# DomoDinV1_0.net
KiCad netlist of a schematic drawn in EAGLE
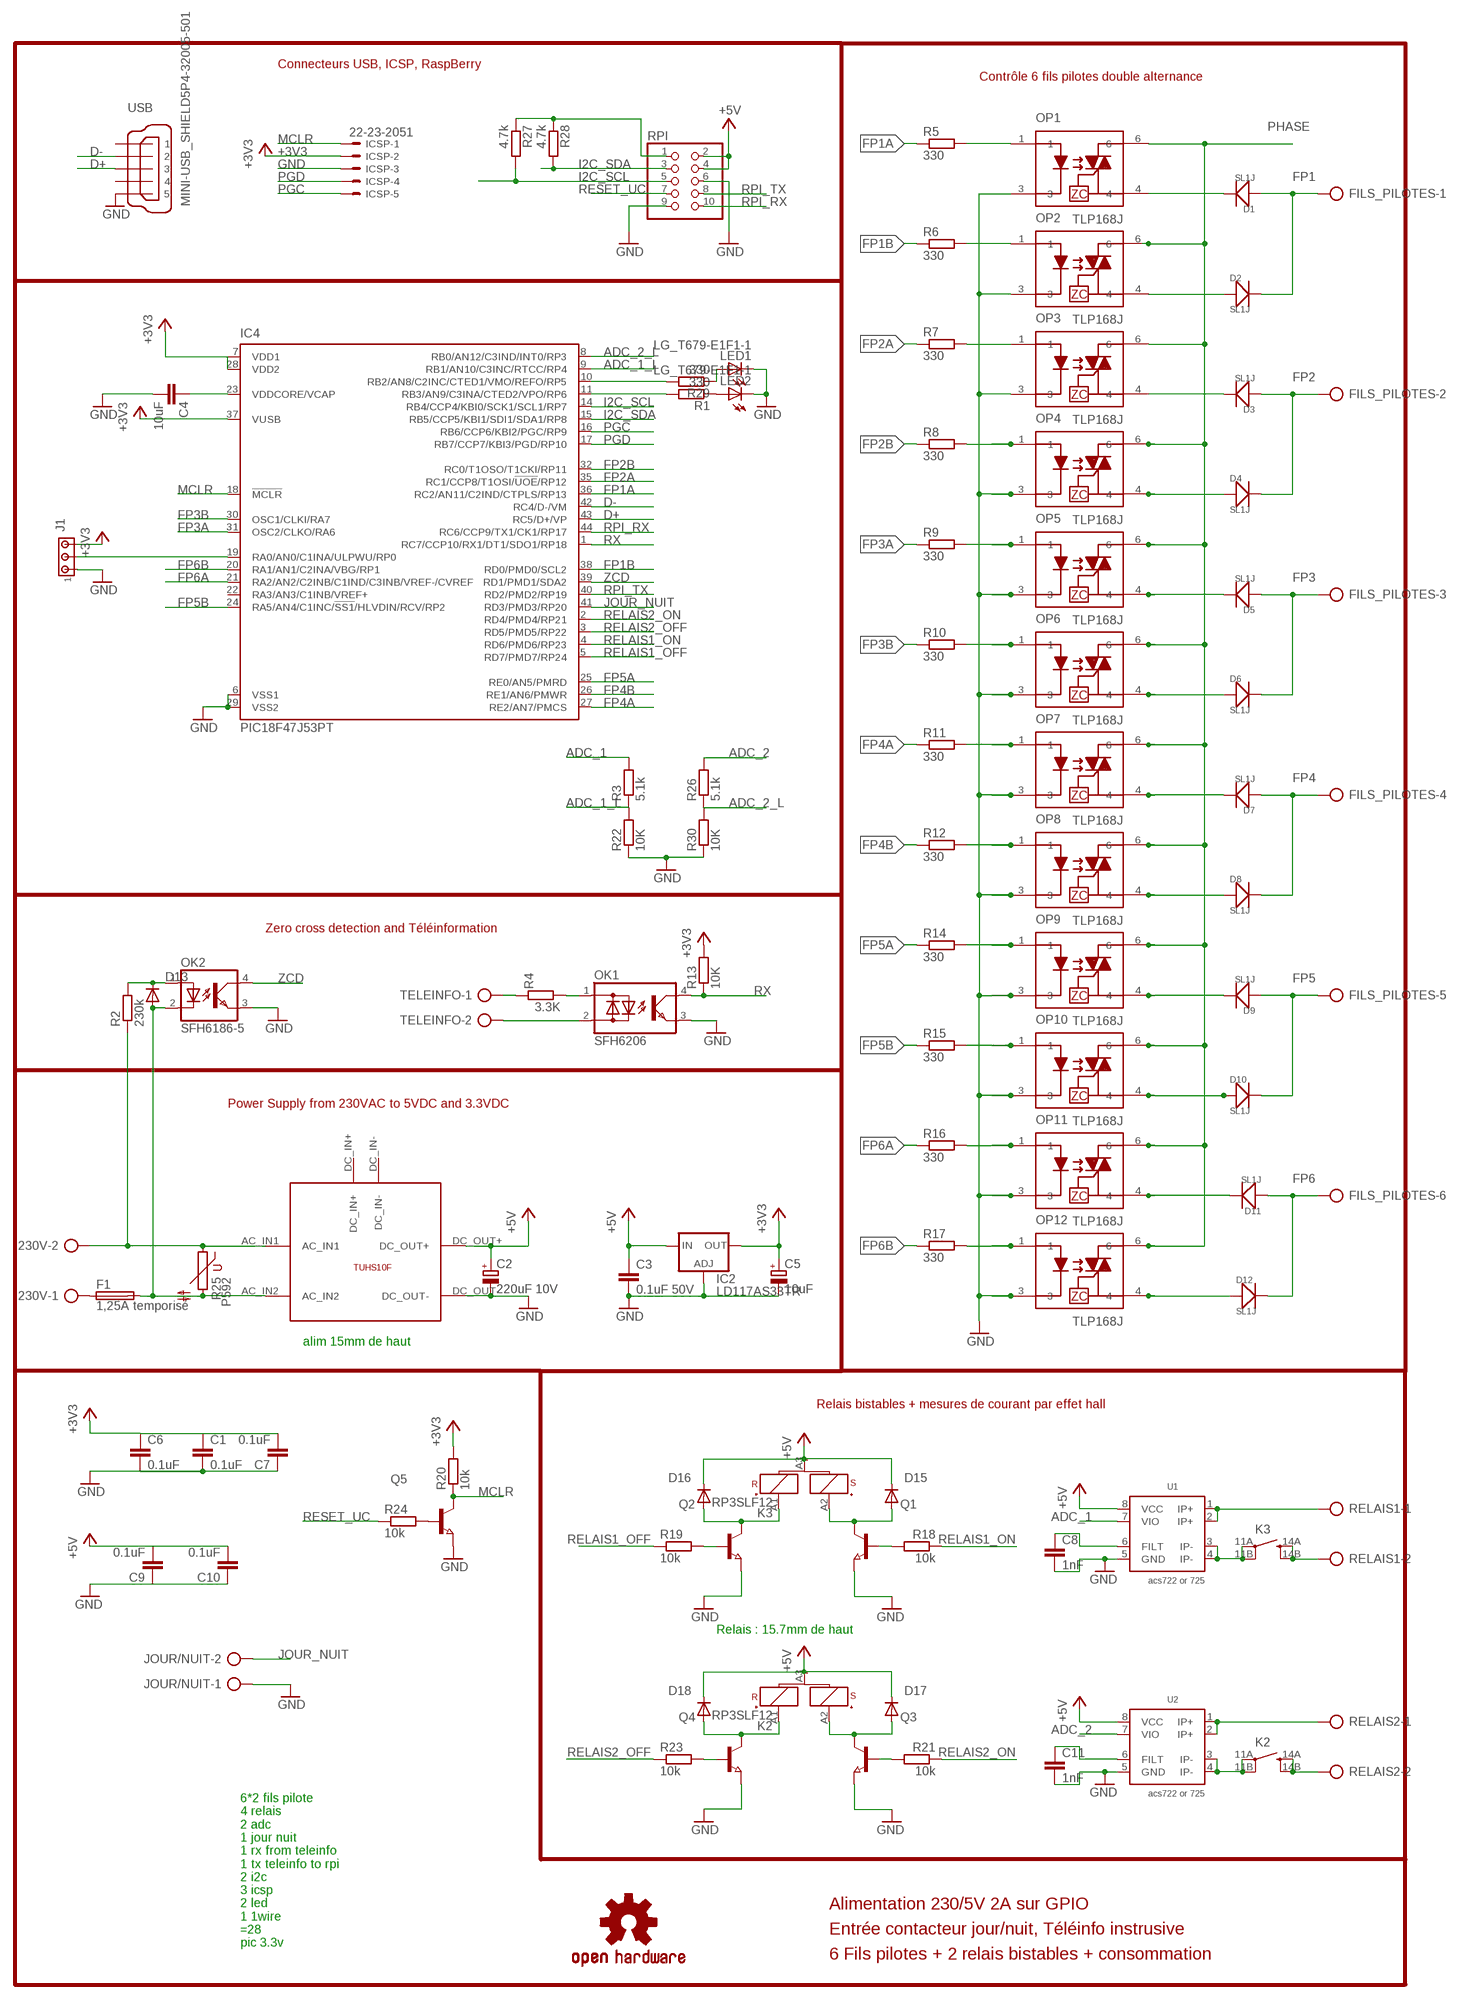
[diagram p0: schematic, sheet 1]

(export (version "E")
  (design (tool "Eeschema 10.0.6"))
  (components
    (comp (ref "230V")
      (value "AK500/2")
      (footprint "eagle-import:AK500_2")
      (libsource (lib "eagle-import") (part "AK500/2"))
    )
    (comp (ref "C1")
      (value "0.1uF")
      (footprint "eagle-import:C0603")
      (libsource (lib "eagle-import") (part "C-EUC0603"))
    )
    (comp (ref "C2")
      (value "220uF 10V")
      (footprint "eagle-import:E5-8,5")
      (libsource (lib "eagle-import") (part "CPOL-EUE5-8.5"))
    )
    (comp (ref "C3")
      (value "0.1uF 50V")
      (footprint "eagle-import:C1206")
      (libsource (lib "eagle-import") (part "C-EUC1206"))
    )
    (comp (ref "C4")
      (value "10uF")
      (footprint "eagle-import:C1210K")
      (libsource (lib "eagle-import") (part "C-EUC1210K"))
    )
    (comp (ref "C5")
      (value "10uF")
      (footprint "eagle-import:C_6032-28R")
      (libsource (lib "eagle-import") (part "CPOL-EUC/6032-28R"))
    )
    (comp (ref "C6")
      (value "0.1uF")
      (footprint "eagle-import:C0603")
      (libsource (lib "eagle-import") (part "C-EUC0603"))
    )
    (comp (ref "C7")
      (value "0.1uF")
      (footprint "eagle-import:C0603")
      (libsource (lib "eagle-import") (part "C-EUC0603"))
    )
    (comp (ref "C8")
      (value "1nF")
      (footprint "eagle-import:C0402")
      (libsource (lib "eagle-import") (part "C-EUC0402"))
    )
    (comp (ref "C9")
      (value "0.1uF")
      (footprint "eagle-import:C0603")
      (libsource (lib "eagle-import") (part "C-EUC0603"))
    )
    (comp (ref "C10")
      (value "0.1uF")
      (footprint "eagle-import:C0603")
      (libsource (lib "eagle-import") (part "C-EUC0603"))
    )
    (comp (ref "C11")
      (value "1nF")
      (footprint "eagle-import:C0402")
      (libsource (lib "eagle-import") (part "C-EUC0402"))
    )
    (comp (ref "D1")
      (value "SL1J")
      (footprint "eagle-import:DO-214AC")
      (libsource (lib "eagle-import") (part "DIODE-SMA"))
    )
    (comp (ref "D2")
      (value "SL1J")
      (footprint "eagle-import:DO-214AC")
      (libsource (lib "eagle-import") (part "DIODE-SMA"))
    )
    (comp (ref "D3")
      (value "SL1J")
      (footprint "eagle-import:DO-214AC")
      (libsource (lib "eagle-import") (part "DIODE-SMA"))
    )
    (comp (ref "D4")
      (value "SL1J")
      (footprint "eagle-import:DO-214AC")
      (libsource (lib "eagle-import") (part "DIODE-SMA"))
    )
    (comp (ref "D5")
      (value "SL1J")
      (footprint "eagle-import:DO-214AC")
      (libsource (lib "eagle-import") (part "DIODE-SMA"))
    )
    (comp (ref "D6")
      (value "SL1J")
      (footprint "eagle-import:DO-214AC")
      (libsource (lib "eagle-import") (part "DIODE-SMA"))
    )
    (comp (ref "D7")
      (value "SL1J")
      (footprint "eagle-import:DO-214AC")
      (libsource (lib "eagle-import") (part "DIODE-SMA"))
    )
    (comp (ref "D8")
      (value "SL1J")
      (footprint "eagle-import:DO-214AC")
      (libsource (lib "eagle-import") (part "DIODE-SMA"))
    )
    (comp (ref "D9")
      (value "SL1J")
      (footprint "eagle-import:DO-214AC")
      (libsource (lib "eagle-import") (part "DIODE-SMA"))
    )
    (comp (ref "D10")
      (value "SL1J")
      (footprint "eagle-import:DO-214AC")
      (libsource (lib "eagle-import") (part "DIODE-SMA"))
    )
    (comp (ref "D11")
      (value "SL1J")
      (footprint "eagle-import:DO-214AC")
      (libsource (lib "eagle-import") (part "DIODE-SMA"))
    )
    (comp (ref "D12")
      (value "SL1J")
      (footprint "eagle-import:DO-214AC")
      (libsource (lib "eagle-import") (part "DIODE-SMA"))
    )
    (comp (ref "D13")
      (value "CGRM4001-G")
      (footprint "eagle-import:SOD-123_MINI-SMA")
      (libsource (lib "eagle-import") (part "CGRM400-G1"))
    )
    (comp (ref "D15")
      (value "CGRM4001-G")
      (footprint "eagle-import:SOD-123_MINI-SMA")
      (libsource (lib "eagle-import") (part "CGRM400-G1"))
    )
    (comp (ref "D16")
      (value "CGRM4001-G")
      (footprint "eagle-import:SOD-123_MINI-SMA")
      (libsource (lib "eagle-import") (part "CGRM400-G1"))
    )
    (comp (ref "D17")
      (value "CGRM4001-G")
      (footprint "eagle-import:SOD-123_MINI-SMA")
      (libsource (lib "eagle-import") (part "CGRM400-G1"))
    )
    (comp (ref "D18")
      (value "CGRM4001-G")
      (footprint "eagle-import:SOD-123_MINI-SMA")
      (libsource (lib "eagle-import") (part "CGRM400-G1"))
    )
    (comp (ref "F1")
      (value "1,25A temporisé")
      (footprint "eagle-import:TE5")
      (libsource (lib "eagle-import") (part "TE5"))
    )
    (comp (ref "FILS_PILOTES")
      (value "AK500/6")
      (footprint "eagle-import:AK500_6")
      (libsource (lib "eagle-import") (part "AK500/6"))
    )
    (comp (ref "IC2")
      (value "LD117AS33TR")
      (footprint "eagle-import:SOT223")
      (libsource (lib "eagle-import") (part "LD117A?S33TR"))
    )
    (comp (ref "IC4")
      (value "PIC18F47J53PT")
      (footprint "eagle-import:TQFP44")
      (fields (field (name "MPN") "PIC18F47J53-I/PT"))
      (libsource (lib "eagle-import") (part "PIC18F47J53PT"))
    )
    (comp (ref "ICSP")
      (value "22-23-2051")
      (footprint "eagle-import:22-23-2051")
      (fields (field (name "MF") "MOLEX"))
      (libsource (lib "eagle-import") (part "22-23-2051"))
    )
    (comp (ref "J1")
      (value "MTA03-100")
      (footprint "eagle-import:10X03MTA")
      (libsource (lib "eagle-import") (part "MTA03-100"))
    )
    (comp (ref "JOUR/NUIT")
      (value "AK500/2")
      (footprint "eagle-import:AK500_2")
      (libsource (lib "eagle-import") (part "AK500/2"))
    )
    (comp (ref "K2")
      (value "RP3SLF12")
      (footprint "eagle-import:RP-SLF")
      (libsource (lib "eagle-import") (part "RP?SLF312"))
    )
    (comp (ref "K3")
      (value "RP3SLF12")
      (footprint "eagle-import:RP-SLF")
      (libsource (lib "eagle-import") (part "RP?SLF312"))
    )
    (comp (ref "LED1")
      (value "LG_T679-E1F1-1")
      (footprint "eagle-import:PLCC2")
      (libsource (lib "eagle-import") (part "_T679-?-1E1F1LG"))
    )
    (comp (ref "LED2")
      (value "LG_T679-E1F1-1")
      (footprint "eagle-import:PLCC2")
      (libsource (lib "eagle-import") (part "_T679-?-1E1F1LG"))
    )
    (comp (ref "LOGO1")
      (value "OSHW-LOGOL")
      (footprint "eagle-import:OSHW-LOGO-L")
      (libsource (lib "eagle-import") (part "OSHW-LOGOL"))
    )
    (comp (ref "OK1")
      (value "SFH6206")
      (footprint "eagle-import:DIL4-SMD")
      (fields (field (name "MF") "VISHAY/TELEFUNKEN") (field (name "MPN") "SFH6206-3"))
      (libsource (lib "eagle-import") (part "SFH6206"))
    )
    (comp (ref "OK2")
      (value "SFH6186-5")
      (footprint "eagle-import:SMD4-7")
      (fields (field (name "MF") "VISHAY/TELEFUNKEN"))
      (libsource (lib "eagle-import") (part "SFH618?6-5"))
    )
    (comp (ref "OP1")
      (value "TLP168J")
      (footprint "eagle-import:MFSOP-4-HANDSOLDER")
      (libsource (lib "eagle-import") (part "TLP168JBIGPAD"))
    )
    (comp (ref "OP2")
      (value "TLP168J")
      (footprint "eagle-import:MFSOP-4-HANDSOLDER")
      (libsource (lib "eagle-import") (part "TLP168JBIGPAD"))
    )
    (comp (ref "OP3")
      (value "TLP168J")
      (footprint "eagle-import:MFSOP-4-HANDSOLDER")
      (libsource (lib "eagle-import") (part "TLP168JBIGPAD"))
    )
    (comp (ref "OP4")
      (value "TLP168J")
      (footprint "eagle-import:MFSOP-4-HANDSOLDER")
      (libsource (lib "eagle-import") (part "TLP168JBIGPAD"))
    )
    (comp (ref "OP5")
      (value "TLP168J")
      (footprint "eagle-import:MFSOP-4-HANDSOLDER")
      (libsource (lib "eagle-import") (part "TLP168JBIGPAD"))
    )
    (comp (ref "OP6")
      (value "TLP168J")
      (footprint "eagle-import:MFSOP-4-HANDSOLDER")
      (libsource (lib "eagle-import") (part "TLP168JBIGPAD"))
    )
    (comp (ref "OP7")
      (value "TLP168J")
      (footprint "eagle-import:MFSOP-4-HANDSOLDER")
      (libsource (lib "eagle-import") (part "TLP168JBIGPAD"))
    )
    (comp (ref "OP8")
      (value "TLP168J")
      (footprint "eagle-import:MFSOP-4-HANDSOLDER")
      (libsource (lib "eagle-import") (part "TLP168JBIGPAD"))
    )
    (comp (ref "OP9")
      (value "TLP168J")
      (footprint "eagle-import:MFSOP-4-HANDSOLDER")
      (libsource (lib "eagle-import") (part "TLP168JBIGPAD"))
    )
    (comp (ref "OP10")
      (value "TLP168J")
      (footprint "eagle-import:MFSOP-4-HANDSOLDER")
      (libsource (lib "eagle-import") (part "TLP168JBIGPAD"))
    )
    (comp (ref "OP11")
      (value "TLP168J")
      (footprint "eagle-import:MFSOP-4-HANDSOLDER")
      (libsource (lib "eagle-import") (part "TLP168JBIGPAD"))
    )
    (comp (ref "OP12")
      (value "TLP168J")
      (footprint "eagle-import:MFSOP-4-HANDSOLDER")
      (libsource (lib "eagle-import") (part "TLP168JBIGPAD"))
    )
    (comp (ref "Q1")
      (value "NPN-TRANSISTOR_SOT23")
      (footprint "eagle-import:SOT23")
      (libsource (lib "eagle-import") (part "NPN-TRANSISTOR_SOT23"))
    )
    (comp (ref "Q2")
      (value "NPN-TRANSISTOR_SOT23")
      (footprint "eagle-import:SOT23")
      (libsource (lib "eagle-import") (part "NPN-TRANSISTOR_SOT23"))
    )
    (comp (ref "Q3")
      (value "NPN-TRANSISTOR_SOT23")
      (footprint "eagle-import:SOT23")
      (libsource (lib "eagle-import") (part "NPN-TRANSISTOR_SOT23"))
    )
    (comp (ref "Q4")
      (value "NPN-TRANSISTOR_SOT23")
      (footprint "eagle-import:SOT23")
      (libsource (lib "eagle-import") (part "NPN-TRANSISTOR_SOT23"))
    )
    (comp (ref "Q5")
      (value "NPN-TRANSISTOR_SOT23")
      (footprint "eagle-import:SOT23")
      (libsource (lib "eagle-import") (part "NPN-TRANSISTOR_SOT23"))
    )
    (comp (ref "R1")
      (value "330")
      (footprint "eagle-import:R0805")
      (libsource (lib "eagle-import") (part "R-EU_R0805"))
    )
    (comp (ref "R2")
      (value "230k")
      (footprint "eagle-import:0204_7")
      (libsource (lib "eagle-import") (part "R-EU_0204/7"))
    )
    (comp (ref "R3")
      (value "5.1k")
      (footprint "eagle-import:R0402")
      (libsource (lib "eagle-import") (part "R-EU_R0402"))
    )
    (comp (ref "R4")
      (value "3.3K")
      (footprint "eagle-import:R0805")
      (libsource (lib "eagle-import") (part "R-EU_R0805"))
    )
    (comp (ref "R5")
      (value "330")
      (footprint "eagle-import:R0805")
      (libsource (lib "eagle-import") (part "R-EU_R0805"))
    )
    (comp (ref "R6")
      (value "330")
      (footprint "eagle-import:R0805")
      (libsource (lib "eagle-import") (part "R-EU_R0805"))
    )
    (comp (ref "R7")
      (value "330")
      (footprint "eagle-import:R0805")
      (libsource (lib "eagle-import") (part "R-EU_R0805"))
    )
    (comp (ref "R8")
      (value "330")
      (footprint "eagle-import:R0805")
      (libsource (lib "eagle-import") (part "R-EU_R0805"))
    )
    (comp (ref "R9")
      (value "330")
      (footprint "eagle-import:R0805")
      (libsource (lib "eagle-import") (part "R-EU_R0805"))
    )
    (comp (ref "R10")
      (value "330")
      (footprint "eagle-import:R0805")
      (libsource (lib "eagle-import") (part "R-EU_R0805"))
    )
    (comp (ref "R11")
      (value "330")
      (footprint "eagle-import:R0805")
      (libsource (lib "eagle-import") (part "R-EU_R0805"))
    )
    (comp (ref "R12")
      (value "330")
      (footprint "eagle-import:R0805")
      (libsource (lib "eagle-import") (part "R-EU_R0805"))
    )
    (comp (ref "R13")
      (value "10K")
      (footprint "eagle-import:R0805")
      (libsource (lib "eagle-import") (part "R-EU_R0805"))
    )
    (comp (ref "R14")
      (value "330")
      (footprint "eagle-import:R0805")
      (libsource (lib "eagle-import") (part "R-EU_R0805"))
    )
    (comp (ref "R15")
      (value "330")
      (footprint "eagle-import:R0805")
      (libsource (lib "eagle-import") (part "R-EU_R0805"))
    )
    (comp (ref "R16")
      (value "330")
      (footprint "eagle-import:R0805")
      (libsource (lib "eagle-import") (part "R-EU_R0805"))
    )
    (comp (ref "R17")
      (value "330")
      (footprint "eagle-import:R0805")
      (libsource (lib "eagle-import") (part "R-EU_R0805"))
    )
    (comp (ref "R18")
      (value "10k")
      (footprint "eagle-import:R0805")
      (libsource (lib "eagle-import") (part "R-EU_R0805"))
    )
    (comp (ref "R19")
      (value "10k")
      (footprint "eagle-import:R0805")
      (libsource (lib "eagle-import") (part "R-EU_R0805"))
    )
    (comp (ref "R20")
      (value "10k")
      (footprint "eagle-import:R0805")
      (libsource (lib "eagle-import") (part "R-EU_R0805"))
    )
    (comp (ref "R21")
      (value "10k")
      (footprint "eagle-import:R0805")
      (libsource (lib "eagle-import") (part "R-EU_R0805"))
    )
    (comp (ref "R22")
      (value "10K")
      (footprint "eagle-import:R0402")
      (libsource (lib "eagle-import") (part "R-EU_R0402"))
    )
    (comp (ref "R23")
      (value "10k")
      (footprint "eagle-import:R0805")
      (libsource (lib "eagle-import") (part "R-EU_R0805"))
    )
    (comp (ref "R24")
      (value "10k")
      (footprint "eagle-import:R0805")
      (libsource (lib "eagle-import") (part "R-EU_R0805"))
    )
    (comp (ref "R25")
      (value "P592")
      (footprint "eagle-import:P592")
      (libsource (lib "eagle-import") (part "P592"))
    )
    (comp (ref "R26")
      (value "5.1k")
      (footprint "eagle-import:R0402")
      (libsource (lib "eagle-import") (part "R-EU_R0402"))
    )
    (comp (ref "R27")
      (value "4.7k")
      (footprint "eagle-import:R0805")
      (libsource (lib "eagle-import") (part "R-EU_R0805"))
    )
    (comp (ref "R28")
      (value "4.7k")
      (footprint "eagle-import:R0805")
      (libsource (lib "eagle-import") (part "R-EU_R0805"))
    )
    (comp (ref "R29")
      (value "330")
      (footprint "eagle-import:R0805")
      (libsource (lib "eagle-import") (part "R-EU_R0805"))
    )
    (comp (ref "R30")
      (value "10K")
      (footprint "eagle-import:R0402")
      (libsource (lib "eagle-import") (part "R-EU_R0402"))
    )
    (comp (ref "RELAIS1")
      (value "AK500/2")
      (footprint "eagle-import:AK500_2")
      (libsource (lib "eagle-import") (part "AK500/2"))
    )
    (comp (ref "RELAIS2")
      (value "AK500/2")
      (footprint "eagle-import:AK500_2")
      (libsource (lib "eagle-import") (part "AK500/2"))
    )
    (comp (ref "RPI")
      (value "PINHD-2X5")
      (footprint "eagle-import:2X05")
      (libsource (lib "eagle-import") (part "PINHD-2X5"))
    )
    (comp (ref "TELEINFO")
      (value "AK500/2")
      (footprint "eagle-import:AK500_2")
      (libsource (lib "eagle-import") (part "AK500/2"))
    )
    (comp (ref "U$1")
      (value "TUHS10F")
      (footprint "eagle-import:TUHS10F05")
      (libsource (lib "eagle-import") (part "TUHS10F"))
    )
    (comp (ref "U1")
      (value "acs722 or 725")
      (footprint "eagle-import:SO08")
      (libsource (lib "eagle-import") (part "ACS712"))
    )
    (comp (ref "U2")
      (value "acs722 or 725")
      (footprint "eagle-import:SO08")
      (libsource (lib "eagle-import") (part "ACS712"))
    )
    (comp (ref "USB")
      (value "MINI-USB_SHIELD5P4-32005-501")
      (footprint "eagle-import:32005-501")
      (libsource (lib "eagle-import") (part "MINI-USB_SHIELD5P4-32005-501"))
    )
  )
  (nets
    (net (code "1") (name "+3V3") (class "Default")
      (node (ref "C1") (pin "1") (pinfunction "1_1") (pintype "passive"))
      (node (ref "C5") (pin "+") (pinfunction "+_+") (pintype "passive"))
      (node (ref "C6") (pin "1") (pinfunction "1_1") (pintype "passive"))
      (node (ref "C7") (pin "2") (pinfunction "2_2") (pintype "passive"))
      (node (ref "IC2") (pin "4") (pinfunction "OUT_4") (pintype "passive"))
      (node (ref "IC4") (pin "28") (pinfunction "VDD2_28") (pintype "input"))
      (node (ref "IC4") (pin "37") (pinfunction "VUSB_37") (pintype "input"))
      (node (ref "IC4") (pin "7") (pinfunction "VDD1_7") (pintype "input"))
      (node (ref "ICSP") (pin "2") (pinfunction "S_2") (pintype "passive"))
      (node (ref "J1") (pin "3") (pinfunction "3_3") (pintype "passive"))
      (node (ref "R13") (pin "2") (pinfunction "2_2") (pintype "passive"))
      (node (ref "R20") (pin "2") (pinfunction "2_2") (pintype "passive"))
    )
    (net (code "2") (name "+5V") (class "Default")
      (node (ref "C10") (pin "2") (pinfunction "2_2") (pintype "passive"))
      (node (ref "C2") (pin "+") (pinfunction "+_+") (pintype "passive"))
      (node (ref "C3") (pin "1") (pinfunction "1_1") (pintype "passive"))
      (node (ref "C9") (pin "2") (pinfunction "2_2") (pintype "passive"))
      (node (ref "D15") (pin "C") (pinfunction "C_C") (pintype "passive"))
      (node (ref "D16") (pin "C") (pinfunction "C_C") (pintype "passive"))
      (node (ref "D17") (pin "C") (pinfunction "C_C") (pintype "passive"))
      (node (ref "D18") (pin "C") (pinfunction "C_C") (pintype "passive"))
      (node (ref "IC2") (pin "3") (pinfunction "IN_3") (pintype "input"))
      (node (ref "K2") (pin "A3") (pinfunction "-_A3") (pintype "passive"))
      (node (ref "K3") (pin "A3") (pinfunction "-_A3") (pintype "passive"))
      (node (ref "RPI") (pin "2") (pinfunction "2_2") (pintype "passive"))
      (node (ref "RPI") (pin "4") (pinfunction "4_4") (pintype "passive"))
      (node (ref "U$1") (pin "DC_OUT+") (pinfunction "DC_OUT+_DC_OUT+") (pintype "bidirectional"))
      (node (ref "U1") (pin "8") (pinfunction "VCC_8") (pintype "bidirectional"))
      (node (ref "U2") (pin "8") (pinfunction "VCC_8") (pintype "bidirectional"))
    )
    (net (code "3") (name "/ADC_1") (class "Default")
      (node (ref "R3") (pin "2") (pinfunction "2_2") (pintype "passive"))
      (node (ref "U1") (pin "7") (pinfunction "VIO_7") (pintype "bidirectional"))
    )
    (net (code "4") (name "/ADC_1_L") (class "Default")
      (node (ref "IC4") (pin "9") (pinfunction "RB1/AN10/C3INC/RTCC/RP4_9") (pintype "bidirectional"))
      (node (ref "R22") (pin "2") (pinfunction "2_2") (pintype "passive"))
      (node (ref "R3") (pin "1") (pinfunction "1_1") (pintype "passive"))
    )
    (net (code "5") (name "/ADC_2") (class "Default")
      (node (ref "R26") (pin "2") (pinfunction "2_2") (pintype "passive"))
      (node (ref "U2") (pin "7") (pinfunction "VIO_7") (pintype "bidirectional"))
    )
    (net (code "6") (name "/ADC_2_L") (class "Default")
      (node (ref "IC4") (pin "8") (pinfunction "RB0/AN12/C3IND/INT0/RP3_8") (pintype "bidirectional"))
      (node (ref "R26") (pin "1") (pinfunction "1_1") (pintype "passive"))
      (node (ref "R30") (pin "2") (pinfunction "2_2") (pintype "passive"))
    )
    (net (code "7") (name "/D+") (class "Default")
      (node (ref "IC4") (pin "43") (pinfunction "RC5/D+/VP_43") (pintype "bidirectional"))
      (node (ref "USB") (pin "3") (pinfunction "3_3") (pintype "passive"))
    )
    (net (code "8") (name "/D-") (class "Default")
      (node (ref "IC4") (pin "42") (pinfunction "RC4/D-/VM_42") (pintype "bidirectional"))
      (node (ref "USB") (pin "2") (pinfunction "2_2") (pintype "passive"))
    )
    (net (code "9") (name "/FP1") (class "Default")
      (node (ref "D1") (pin "1") (pinfunction "+_1") (pintype "passive"))
      (node (ref "D2") (pin "2") (pinfunction "-_2") (pintype "passive"))
      (node (ref "FILS_PILOTES") (pin "1") (pinfunction "KL_1") (pintype "passive"))
    )
    (net (code "10") (name "/FP2") (class "Default")
      (node (ref "D3") (pin "1") (pinfunction "+_1") (pintype "passive"))
      (node (ref "D4") (pin "2") (pinfunction "-_2") (pintype "passive"))
      (node (ref "FILS_PILOTES") (pin "2") (pinfunction "KL_2") (pintype "passive"))
    )
    (net (code "11") (name "/FP3") (class "Default")
      (node (ref "D5") (pin "1") (pinfunction "+_1") (pintype "passive"))
      (node (ref "D6") (pin "2") (pinfunction "-_2") (pintype "passive"))
      (node (ref "FILS_PILOTES") (pin "3") (pinfunction "KL_3") (pintype "passive"))
    )
    (net (code "12") (name "/FP4") (class "Default")
      (node (ref "D7") (pin "1") (pinfunction "+_1") (pintype "passive"))
      (node (ref "D8") (pin "2") (pinfunction "-_2") (pintype "passive"))
      (node (ref "FILS_PILOTES") (pin "4") (pinfunction "KL_4") (pintype "passive"))
    )
    (net (code "13") (name "/FP5") (class "Default")
      (node (ref "D10") (pin "2") (pinfunction "-_2") (pintype "passive"))
      (node (ref "D9") (pin "1") (pinfunction "+_1") (pintype "passive"))
      (node (ref "FILS_PILOTES") (pin "5") (pinfunction "KL_5") (pintype "passive"))
    )
    (net (code "14") (name "/FP6") (class "Default")
      (node (ref "D11") (pin "1") (pinfunction "+_1") (pintype "passive"))
      (node (ref "D12") (pin "2") (pinfunction "-_2") (pintype "passive"))
      (node (ref "FILS_PILOTES") (pin "6") (pinfunction "KL_6") (pintype "passive"))
    )
    (net (code "15") (name "/I2C_SCL") (class "Default")
      (node (ref "IC4") (pin "14") (pinfunction "RB4/CCP4/KBI0/SCK1/SCL1/RP7_14") (pintype "bidirectional"))
      (node (ref "R27") (pin "2") (pinfunction "2_2") (pintype "passive"))
      (node (ref "RPI") (pin "5") (pinfunction "5_5") (pintype "passive"))
    )
    (net (code "16") (name "/I2C_SDA") (class "Default")
      (node (ref "IC4") (pin "15") (pinfunction "RB5/CCP5/KBI1/SDI1/SDA1/RP8_15") (pintype "bidirectional"))
      (node (ref "R28") (pin "2") (pinfunction "2_2") (pintype "passive"))
      (node (ref "RPI") (pin "3") (pinfunction "3_3") (pintype "passive"))
    )
    (net (code "17") (name "/JOUR_NUIT") (class "Default")
      (node (ref "IC4") (pin "41") (pinfunction "RD3/PMD3/RP20_41") (pintype "bidirectional"))
      (node (ref "JOUR/NUIT") (pin "2") (pinfunction "KL_2") (pintype "passive"))
    )
    (net (code "18") (name "/MCLR") (class "Default")
      (node (ref "IC4") (pin "18") (pinfunction "~{MCLR}_18") (pintype "input"))
      (node (ref "ICSP") (pin "1") (pinfunction "S_1") (pintype "passive"))
      (node (ref "Q5") (pin "3") (pinfunction "C_3") (pintype "passive"))
      (node (ref "R20") (pin "1") (pinfunction "1_1") (pintype "passive"))
    )
    (net (code "19") (name "/PGC") (class "Default")
      (node (ref "IC4") (pin "16") (pinfunction "RB6/CCP6/KBI2/PGC/RP9_16") (pintype "bidirectional"))
      (node (ref "ICSP") (pin "5") (pinfunction "S_5") (pintype "passive"))
    )
    (net (code "20") (name "/PGD") (class "Default")
      (node (ref "IC4") (pin "17") (pinfunction "RB7/CCP7/KBI3/PGD/RP10_17") (pintype "bidirectional"))
      (node (ref "ICSP") (pin "4") (pinfunction "S_4") (pintype "passive"))
    )
    (net (code "21") (name "/PHASE") (class "Default")
      (node (ref "D13") (pin "A") (pinfunction "A_A") (pintype "passive"))
      (node (ref "F1") (pin "2") (pinfunction "2_2") (pintype "passive"))
      (node (ref "OK2") (pin "2") (pinfunction "C_2") (pintype "passive"))
      (node (ref "OP1") (pin "6") (pinfunction "6_6") (pintype "bidirectional"))
      (node (ref "OP10") (pin "6") (pinfunction "6_6") (pintype "bidirectional"))
      (node (ref "OP11") (pin "6") (pinfunction "6_6") (pintype "bidirectional"))
      (node (ref "OP12") (pin "6") (pinfunction "6_6") (pintype "bidirectional"))
      (node (ref "OP2") (pin "6") (pinfunction "6_6") (pintype "bidirectional"))
      (node (ref "OP3") (pin "6") (pinfunction "6_6") (pintype "bidirectional"))
      (node (ref "OP4") (pin "6") (pinfunction "6_6") (pintype "bidirectional"))
      (node (ref "OP5") (pin "6") (pinfunction "6_6") (pintype "bidirectional"))
      (node (ref "OP6") (pin "6") (pinfunction "6_6") (pintype "bidirectional"))
      (node (ref "OP7") (pin "6") (pinfunction "6_6") (pintype "bidirectional"))
      (node (ref "OP8") (pin "6") (pinfunction "6_6") (pintype "bidirectional"))
      (node (ref "OP9") (pin "6") (pinfunction "6_6") (pintype "bidirectional"))
      (node (ref "R25") (pin "2") (pinfunction "2_2") (pintype "passive"))
      (node (ref "U$1") (pin "AC_IN2") (pinfunction "AC_IN2_AC_IN2") (pintype "bidirectional"))
    )
    (net (code "22") (name "/RELAIS1_OFF") (class "Default")
      (node (ref "IC4") (pin "5") (pinfunction "RD7/PMD7/RP24_5") (pintype "bidirectional"))
      (node (ref "R19") (pin "1") (pinfunction "1_1") (pintype "passive"))
    )
    (net (code "23") (name "/RELAIS1_ON") (class "Default")
      (node (ref "IC4") (pin "4") (pinfunction "RD6/PMD6/RP23_4") (pintype "bidirectional"))
      (node (ref "R18") (pin "1") (pinfunction "1_1") (pintype "passive"))
    )
    (net (code "24") (name "/RELAIS2_OFF") (class "Default")
      (node (ref "IC4") (pin "3") (pinfunction "RD5/PMD5/RP22_3") (pintype "bidirectional"))
      (node (ref "R23") (pin "1") (pinfunction "1_1") (pintype "passive"))
    )
    (net (code "25") (name "/RELAIS2_ON") (class "Default")
      (node (ref "IC4") (pin "2") (pinfunction "RD4/PMD4/RP21_2") (pintype "bidirectional"))
      (node (ref "R21") (pin "1") (pinfunction "1_1") (pintype "passive"))
    )
    (net (code "26") (name "/RESET_UC") (class "Default")
      (node (ref "R24") (pin "1") (pinfunction "1_1") (pintype "passive"))
      (node (ref "RPI") (pin "7") (pinfunction "7_7") (pintype "passive"))
    )
    (net (code "27") (name "/RPI_RX") (class "Default")
      (node (ref "IC4") (pin "44") (pinfunction "RC6/CCP9/TX1/CK1/RP17_44") (pintype "bidirectional"))
      (node (ref "RPI") (pin "10") (pinfunction "10_10") (pintype "passive"))
    )
    (net (code "28") (name "/RPI_TX") (class "Default")
      (node (ref "IC4") (pin "40") (pinfunction "RD2/PMD2/RP19_40") (pintype "bidirectional"))
      (node (ref "RPI") (pin "8") (pinfunction "8_8") (pintype "passive"))
    )
    (net (code "29") (name "/RX") (class "Default")
      (node (ref "IC4") (pin "1") (pinfunction "RC7/CCP10/RX1/DT1/SDO1/RP18_1") (pintype "bidirectional"))
      (node (ref "OK1") (pin "4") (pinfunction "C_4") (pintype "passive"))
      (node (ref "R13") (pin "1") (pinfunction "1_1") (pintype "passive"))
    )
    (net (code "30") (name "/ZCD") (class "Default")
      (node (ref "IC4") (pin "39") (pinfunction "RD1/PMD1/SDA2_39") (pintype "bidirectional"))
      (node (ref "OK2") (pin "4") (pinfunction "COL_4") (pintype "passive"))
    )
    (net (code "31") (name "FP1A") (class "Default")
      (node (ref "IC4") (pin "36") (pinfunction "RC2/AN11/C2IND/CTPLS/RP13_36") (pintype "bidirectional"))
      (node (ref "R5") (pin "1") (pinfunction "1_1") (pintype "passive"))
    )
    (net (code "32") (name "FP1B") (class "Default")
      (node (ref "IC4") (pin "38") (pinfunction "RD0/PMD0/SCL2_38") (pintype "bidirectional"))
      (node (ref "R6") (pin "1") (pinfunction "1_1") (pintype "passive"))
    )
    (net (code "33") (name "FP2A") (class "Default")
      (node (ref "IC4") (pin "35") (pinfunction "RC1/CCP8/T1OSI/~{UOE}/RP12_35") (pintype "bidirectional"))
      (node (ref "R7") (pin "1") (pinfunction "1_1") (pintype "passive"))
    )
    (net (code "34") (name "FP2B") (class "Default")
      (node (ref "IC4") (pin "32") (pinfunction "RC0/T1OSO/T1CKI/RP11_32") (pintype "bidirectional"))
      (node (ref "R8") (pin "1") (pinfunction "1_1") (pintype "passive"))
    )
    (net (code "35") (name "FP3A") (class "Default")
      (node (ref "IC4") (pin "31") (pinfunction "OSC2/CLKO/RA6_31") (pintype "bidirectional"))
      (node (ref "R9") (pin "1") (pinfunction "1_1") (pintype "passive"))
    )
    (net (code "36") (name "FP3B") (class "Default")
      (node (ref "IC4") (pin "30") (pinfunction "OSC1/CLKI/RA7_30") (pintype "bidirectional"))
      (node (ref "R10") (pin "1") (pinfunction "1_1") (pintype "passive"))
    )
    (net (code "37") (name "FP4A") (class "Default")
      (node (ref "IC4") (pin "27") (pinfunction "RE2/AN7/PMCS_27") (pintype "bidirectional"))
      (node (ref "R11") (pin "1") (pinfunction "1_1") (pintype "passive"))
    )
    (net (code "38") (name "FP4B") (class "Default")
      (node (ref "IC4") (pin "26") (pinfunction "RE1/AN6/PMWR_26") (pintype "bidirectional"))
      (node (ref "R12") (pin "1") (pinfunction "1_1") (pintype "passive"))
    )
    (net (code "39") (name "FP5A") (class "Default")
      (node (ref "IC4") (pin "25") (pinfunction "RE0/AN5/PMRD_25") (pintype "bidirectional"))
      (node (ref "R14") (pin "1") (pinfunction "1_1") (pintype "passive"))
    )
    (net (code "40") (name "FP5B") (class "Default")
      (node (ref "IC4") (pin "24") (pinfunction "RA5/AN4/C1INC/~{SS1}/HLVDIN/RCV/RP2_24") (pintype "bidirectional"))
      (node (ref "R15") (pin "1") (pinfunction "1_1") (pintype "passive"))
    )
    (net (code "41") (name "FP6A") (class "Default")
      (node (ref "IC4") (pin "21") (pinfunction "RA2/AN2/C2INB/C1IND/C3INB/VREF-/CVREF_21") (pintype "bidirectional"))
      (node (ref "R16") (pin "1") (pinfunction "1_1") (pintype "passive"))
    )
    (net (code "42") (name "FP6B") (class "Default")
      (node (ref "IC4") (pin "20") (pinfunction "RA1/AN1/C2INA/VBG/RP1_20") (pintype "bidirectional"))
      (node (ref "R17") (pin "1") (pinfunction "1_1") (pintype "passive"))
    )
    (net (code "43") (name "GND") (class "Default")
      (node (ref "C1") (pin "2") (pinfunction "2_2") (pintype "passive"))
      (node (ref "C10") (pin "1") (pinfunction "1_1") (pintype "passive"))
      (node (ref "C11") (pin "2") (pinfunction "2_2") (pintype "passive"))
      (node (ref "C2") (pin "-") (pinfunction "-_-") (pintype "passive"))
      (node (ref "C3") (pin "2") (pinfunction "2_2") (pintype "passive"))
      (node (ref "C4") (pin "2") (pinfunction "2_2") (pintype "passive"))
      (node (ref "C5") (pin "-") (pinfunction "-_-") (pintype "passive"))
      (node (ref "C6") (pin "2") (pinfunction "2_2") (pintype "passive"))
      (node (ref "C7") (pin "1") (pinfunction "1_1") (pintype "passive"))
      (node (ref "C8") (pin "2") (pinfunction "2_2") (pintype "passive"))
      (node (ref "C9") (pin "1") (pinfunction "1_1") (pintype "passive"))
      (node (ref "IC2") (pin "1") (pinfunction "ADJ_1") (pintype "input"))
      (node (ref "IC4") (pin "29") (pinfunction "VSS2_29") (pintype "input"))
      (node (ref "IC4") (pin "6") (pinfunction "VSS1_6") (pintype "input"))
      (node (ref "ICSP") (pin "3") (pinfunction "S_3") (pintype "passive"))
      (node (ref "J1") (pin "1") (pinfunction "1_1") (pintype "passive"))
      (node (ref "JOUR/NUIT") (pin "1") (pinfunction "KL_1") (pintype "passive"))
      (node (ref "LED1") (pin "C") (pinfunction "C_C") (pintype "passive"))
      (node (ref "LED2") (pin "C") (pinfunction "C_C") (pintype "passive"))
      (node (ref "OK1") (pin "3") (pinfunction "E_3") (pintype "passive"))
      (node (ref "OK2") (pin "3") (pinfunction "EMIT_3") (pintype "passive"))
      (node (ref "OP1") (pin "3") (pinfunction "3_3") (pintype "bidirectional"))
      (node (ref "OP10") (pin "3") (pinfunction "3_3") (pintype "bidirectional"))
      (node (ref "OP11") (pin "3") (pinfunction "3_3") (pintype "bidirectional"))
      (node (ref "OP12") (pin "3") (pinfunction "3_3") (pintype "bidirectional"))
      (node (ref "OP2") (pin "3") (pinfunction "3_3") (pintype "bidirectional"))
      (node (ref "OP3") (pin "3") (pinfunction "3_3") (pintype "bidirectional"))
      (node (ref "OP4") (pin "3") (pinfunction "3_3") (pintype "bidirectional"))
      (node (ref "OP5") (pin "3") (pinfunction "3_3") (pintype "bidirectional"))
      (node (ref "OP6") (pin "3") (pinfunction "3_3") (pintype "bidirectional"))
      (node (ref "OP7") (pin "3") (pinfunction "3_3") (pintype "bidirectional"))
      (node (ref "OP8") (pin "3") (pinfunction "3_3") (pintype "bidirectional"))
      (node (ref "OP9") (pin "3") (pinfunction "3_3") (pintype "bidirectional"))
      (node (ref "Q1") (pin "2") (pinfunction "E_2") (pintype "passive"))
      (node (ref "Q2") (pin "2") (pinfunction "E_2") (pintype "passive"))
      (node (ref "Q3") (pin "2") (pinfunction "E_2") (pintype "passive"))
      (node (ref "Q4") (pin "2") (pinfunction "E_2") (pintype "passive"))
      (node (ref "Q5") (pin "2") (pinfunction "E_2") (pintype "passive"))
      (node (ref "R22") (pin "1") (pinfunction "1_1") (pintype "passive"))
      (node (ref "R30") (pin "1") (pinfunction "1_1") (pintype "passive"))
      (node (ref "RPI") (pin "6") (pinfunction "6_6") (pintype "passive"))
      (node (ref "RPI") (pin "9") (pinfunction "9_9") (pintype "passive"))
      (node (ref "U$1") (pin "DC_OUT-") (pinfunction "DC_OUT-_DC_OUT-") (pintype "bidirectional"))
      (node (ref "U1") (pin "5") (pinfunction "GND_5") (pintype "bidirectional"))
      (node (ref "U2") (pin "5") (pinfunction "GND_5") (pintype "bidirectional"))
      (node (ref "USB") (pin "5") (pinfunction "5_5") (pintype "passive"))
    )
    (net (code "44") (name "Net-(230VA-KL)") (class "Default")
      (node (ref "230V") (pin "1") (pinfunction "KL_1") (pintype "passive"))
      (node (ref "F1") (pin "1") (pinfunction "1_1") (pintype "passive"))
    )
    (net (code "45") (name "Net-(230VB-KL)") (class "Default")
      (node (ref "230V") (pin "2") (pinfunction "KL_2") (pintype "passive"))
      (node (ref "R2") (pin "1") (pinfunction "1_1") (pintype "passive"))
      (node (ref "R25") (pin "1") (pinfunction "1_1") (pintype "passive"))
      (node (ref "U$1") (pin "AC_IN1") (pinfunction "AC_IN1_AC_IN1") (pintype "bidirectional"))
    )
    (net (code "46") (name "Net-(D1--)") (class "Default")
      (node (ref "D1") (pin "2") (pinfunction "-_2") (pintype "passive"))
      (node (ref "OP1") (pin "4") (pinfunction "4_4") (pintype "bidirectional"))
    )
    (net (code "47") (name "Net-(D2-+)") (class "Default")
      (node (ref "D2") (pin "1") (pinfunction "+_1") (pintype "passive"))
      (node (ref "OP2") (pin "4") (pinfunction "4_4") (pintype "bidirectional"))
    )
    (net (code "48") (name "Net-(D3--)") (class "Default")
      (node (ref "D3") (pin "2") (pinfunction "-_2") (pintype "passive"))
      (node (ref "OP3") (pin "4") (pinfunction "4_4") (pintype "bidirectional"))
    )
    (net (code "49") (name "Net-(D4-+)") (class "Default")
      (node (ref "D4") (pin "1") (pinfunction "+_1") (pintype "passive"))
      (node (ref "OP4") (pin "4") (pinfunction "4_4") (pintype "bidirectional"))
    )
    (net (code "50") (name "Net-(D5--)") (class "Default")
      (node (ref "D5") (pin "2") (pinfunction "-_2") (pintype "passive"))
      (node (ref "OP5") (pin "4") (pinfunction "4_4") (pintype "bidirectional"))
    )
    (net (code "51") (name "Net-(D6-+)") (class "Default")
      (node (ref "D6") (pin "1") (pinfunction "+_1") (pintype "passive"))
      (node (ref "OP6") (pin "4") (pinfunction "4_4") (pintype "bidirectional"))
    )
    (net (code "52") (name "Net-(D7--)") (class "Default")
      (node (ref "D7") (pin "2") (pinfunction "-_2") (pintype "passive"))
      (node (ref "OP7") (pin "4") (pinfunction "4_4") (pintype "bidirectional"))
    )
    (net (code "53") (name "Net-(D8-+)") (class "Default")
      (node (ref "D8") (pin "1") (pinfunction "+_1") (pintype "passive"))
      (node (ref "OP8") (pin "4") (pinfunction "4_4") (pintype "bidirectional"))
    )
    (net (code "54") (name "Net-(D9--)") (class "Default")
      (node (ref "D9") (pin "2") (pinfunction "-_2") (pintype "passive"))
      (node (ref "OP9") (pin "4") (pinfunction "4_4") (pintype "bidirectional"))
    )
    (net (code "55") (name "Net-(D10-+)") (class "Default")
      (node (ref "D10") (pin "1") (pinfunction "+_1") (pintype "passive"))
      (node (ref "OP10") (pin "4") (pinfunction "4_4") (pintype "bidirectional"))
    )
    (net (code "56") (name "Net-(D11--)") (class "Default")
      (node (ref "D11") (pin "2") (pinfunction "-_2") (pintype "passive"))
      (node (ref "OP11") (pin "4") (pinfunction "4_4") (pintype "bidirectional"))
    )
    (net (code "57") (name "Net-(D12-+)") (class "Default")
      (node (ref "D12") (pin "1") (pinfunction "+_1") (pintype "passive"))
      (node (ref "OP12") (pin "4") (pinfunction "4_4") (pintype "bidirectional"))
    )
    (net (code "58") (name "Net-(IC4-RA0{slash}AN0{slash}C1INA{slash}ULPWU{slash}RP0)") (class "Default")
      (node (ref "IC4") (pin "19") (pinfunction "RA0/AN0/C1INA/ULPWU/RP0_19") (pintype "bidirectional"))
      (node (ref "J1") (pin "2") (pinfunction "2_2") (pintype "passive"))
    )
    (net (code "59") (name "Net-(IC4-RB2{slash}AN8{slash}C2INC{slash}CTED1{slash}VMO{slash}REFO{slash}RP5)") (class "Default")
      (node (ref "IC4") (pin "10") (pinfunction "RB2/AN8/C2INC/CTED1/VMO/REFO/RP5_10") (pintype "bidirectional"))
      (node (ref "R29") (pin "2") (pinfunction "2_2") (pintype "passive"))
    )
    (net (code "60") (name "Net-(IC4-RB3{slash}AN9{slash}C3INA{slash}CTED2{slash}VPO{slash}RP6)") (class "Default")
      (node (ref "IC4") (pin "11") (pinfunction "RB3/AN9/C3INA/CTED2/VPO/RP6_11") (pintype "bidirectional"))
      (node (ref "R1") (pin "2") (pinfunction "2_2") (pintype "passive"))
    )
    (net (code "61") (name "Net-(IC4-VDDCORE{slash}VCAP)") (class "Default")
      (node (ref "C4") (pin "1") (pinfunction "1_1") (pintype "passive"))
      (node (ref "IC4") (pin "23") (pinfunction "VDDCORE/VCAP_23") (pintype "input"))
    )
    (net (code "62") (name "Net-(K2A-R+)") (class "Default")
      (node (ref "D18") (pin "A") (pinfunction "A_A") (pintype "passive"))
      (node (ref "K2") (pin "A1") (pinfunction "R+_A1") (pintype "passive"))
      (node (ref "Q4") (pin "3") (pinfunction "C_3") (pintype "passive"))
    )
    (net (code "63") (name "Net-(K2A-S+)") (class "Default")
      (node (ref "D17") (pin "A") (pinfunction "A_A") (pintype "passive"))
      (node (ref "K2") (pin "A2") (pinfunction "S+_A2") (pintype "passive"))
      (node (ref "Q3") (pin "3") (pinfunction "C_3") (pintype "passive"))
    )
    (net (code "64") (name "Net-(K2B-PA)") (class "Default")
      (node (ref "K2") (pin "11A") (pinfunction "PA_11A") (pintype "passive"))
      (node (ref "K2") (pin "11B") (pinfunction "PB_11B") (pintype "passive"))
      (node (ref "U2") (pin "3") (pinfunction "IP-_3") (pintype "bidirectional"))
      (node (ref "U2") (pin "4") (pinfunction "IP-_4") (pintype "bidirectional"))
    )
    (net (code "65") (name "Net-(K2B-SA)") (class "Default")
      (node (ref "K2") (pin "14A") (pinfunction "SA_14A") (pintype "passive"))
      (node (ref "K2") (pin "14B") (pinfunction "SB_14B") (pintype "passive"))
      (node (ref "RELAIS2") (pin "2") (pinfunction "KL_2") (pintype "passive"))
    )
    (net (code "66") (name "Net-(K3A-R+)") (class "Default")
      (node (ref "D16") (pin "A") (pinfunction "A_A") (pintype "passive"))
      (node (ref "K3") (pin "A1") (pinfunction "R+_A1") (pintype "passive"))
      (node (ref "Q2") (pin "3") (pinfunction "C_3") (pintype "passive"))
    )
    (net (code "67") (name "Net-(K3A-S+)") (class "Default")
      (node (ref "D15") (pin "A") (pinfunction "A_A") (pintype "passive"))
      (node (ref "K3") (pin "A2") (pinfunction "S+_A2") (pintype "passive"))
      (node (ref "Q1") (pin "3") (pinfunction "C_3") (pintype "passive"))
    )
    (net (code "68") (name "Net-(K3B-PA)") (class "Default")
      (node (ref "K3") (pin "11A") (pinfunction "PA_11A") (pintype "passive"))
      (node (ref "K3") (pin "11B") (pinfunction "PB_11B") (pintype "passive"))
      (node (ref "U1") (pin "3") (pinfunction "IP-_3") (pintype "bidirectional"))
      (node (ref "U1") (pin "4") (pinfunction "IP-_4") (pintype "bidirectional"))
    )
    (net (code "69") (name "Net-(K3B-SA)") (class "Default")
      (node (ref "K3") (pin "14A") (pinfunction "SA_14A") (pintype "passive"))
      (node (ref "K3") (pin "14B") (pinfunction "SB_14B") (pintype "passive"))
      (node (ref "RELAIS1") (pin "2") (pinfunction "KL_2") (pintype "passive"))
    )
    (net (code "70") (name "Net-(LED1-PadA)") (class "Default")
      (node (ref "LED1") (pin "A") (pinfunction "A_A") (pintype "passive"))
      (node (ref "R29") (pin "1") (pinfunction "1_1") (pintype "passive"))
    )
    (net (code "71") (name "Net-(LED2-PadA)") (class "Default")
      (node (ref "LED2") (pin "A") (pinfunction "A_A") (pintype "passive"))
      (node (ref "R1") (pin "1") (pinfunction "1_1") (pintype "passive"))
    )
    (net (code "72") (name "Net-(OK1-AC1)") (class "Default")
      (node (ref "OK1") (pin "1") (pinfunction "AC1_1") (pintype "passive"))
      (node (ref "R4") (pin "2") (pinfunction "2_2") (pintype "passive"))
    )
    (net (code "73") (name "Net-(OK1-AC2)") (class "Default")
      (node (ref "OK1") (pin "2") (pinfunction "AC2_2") (pintype "passive"))
      (node (ref "TELEINFO") (pin "2") (pinfunction "KL_2") (pintype "passive"))
    )
    (net (code "74") (name "Net-(OK2-A)") (class "Default")
      (node (ref "D13") (pin "C") (pinfunction "C_C") (pintype "passive"))
      (node (ref "OK2") (pin "1") (pinfunction "A_1") (pintype "passive"))
      (node (ref "R2") (pin "2") (pinfunction "2_2") (pintype "passive"))
    )
    (net (code "75") (name "Net-(OP1-Pad1)") (class "Default")
      (node (ref "OP1") (pin "1") (pinfunction "1_1") (pintype "bidirectional"))
      (node (ref "R5") (pin "2") (pinfunction "2_2") (pintype "passive"))
    )
    (net (code "76") (name "Net-(OP2-Pad1)") (class "Default")
      (node (ref "OP2") (pin "1") (pinfunction "1_1") (pintype "bidirectional"))
      (node (ref "R6") (pin "2") (pinfunction "2_2") (pintype "passive"))
    )
    (net (code "77") (name "Net-(OP3-Pad1)") (class "Default")
      (node (ref "OP3") (pin "1") (pinfunction "1_1") (pintype "bidirectional"))
      (node (ref "R7") (pin "2") (pinfunction "2_2") (pintype "passive"))
    )
    (net (code "78") (name "Net-(OP4-Pad1)") (class "Default")
      (node (ref "OP4") (pin "1") (pinfunction "1_1") (pintype "bidirectional"))
      (node (ref "R8") (pin "2") (pinfunction "2_2") (pintype "passive"))
    )
    (net (code "79") (name "Net-(OP5-Pad1)") (class "Default")
      (node (ref "OP5") (pin "1") (pinfunction "1_1") (pintype "bidirectional"))
      (node (ref "R9") (pin "2") (pinfunction "2_2") (pintype "passive"))
    )
    (net (code "80") (name "Net-(OP6-Pad1)") (class "Default")
      (node (ref "OP6") (pin "1") (pinfunction "1_1") (pintype "bidirectional"))
      (node (ref "R10") (pin "2") (pinfunction "2_2") (pintype "passive"))
    )
    (net (code "81") (name "Net-(OP7-Pad1)") (class "Default")
      (node (ref "OP7") (pin "1") (pinfunction "1_1") (pintype "bidirectional"))
      (node (ref "R11") (pin "2") (pinfunction "2_2") (pintype "passive"))
    )
    (net (code "82") (name "Net-(OP8-Pad1)") (class "Default")
      (node (ref "OP8") (pin "1") (pinfunction "1_1") (pintype "bidirectional"))
      (node (ref "R12") (pin "2") (pinfunction "2_2") (pintype "passive"))
    )
    (net (code "83") (name "Net-(OP9-Pad1)") (class "Default")
      (node (ref "OP9") (pin "1") (pinfunction "1_1") (pintype "bidirectional"))
      (node (ref "R14") (pin "2") (pinfunction "2_2") (pintype "passive"))
    )
    (net (code "84") (name "Net-(OP10-Pad1)") (class "Default")
      (node (ref "OP10") (pin "1") (pinfunction "1_1") (pintype "bidirectional"))
      (node (ref "R15") (pin "2") (pinfunction "2_2") (pintype "passive"))
    )
    (net (code "85") (name "Net-(OP11-Pad1)") (class "Default")
      (node (ref "OP11") (pin "1") (pinfunction "1_1") (pintype "bidirectional"))
      (node (ref "R16") (pin "2") (pinfunction "2_2") (pintype "passive"))
    )
    (net (code "86") (name "Net-(OP12-Pad1)") (class "Default")
      (node (ref "OP12") (pin "1") (pinfunction "1_1") (pintype "bidirectional"))
      (node (ref "R17") (pin "2") (pinfunction "2_2") (pintype "passive"))
    )
    (net (code "87") (name "Net-(Q1-B)") (class "Default")
      (node (ref "Q1") (pin "1") (pinfunction "B_1") (pintype "passive"))
      (node (ref "R18") (pin "2") (pinfunction "2_2") (pintype "passive"))
    )
    (net (code "88") (name "Net-(Q2-B)") (class "Default")
      (node (ref "Q2") (pin "1") (pinfunction "B_1") (pintype "passive"))
      (node (ref "R19") (pin "2") (pinfunction "2_2") (pintype "passive"))
    )
    (net (code "89") (name "Net-(Q3-B)") (class "Default")
      (node (ref "Q3") (pin "1") (pinfunction "B_1") (pintype "passive"))
      (node (ref "R21") (pin "2") (pinfunction "2_2") (pintype "passive"))
    )
    (net (code "90") (name "Net-(Q4-B)") (class "Default")
      (node (ref "Q4") (pin "1") (pinfunction "B_1") (pintype "passive"))
      (node (ref "R23") (pin "2") (pinfunction "2_2") (pintype "passive"))
    )
    (net (code "91") (name "Net-(Q5-B)") (class "Default")
      (node (ref "Q5") (pin "1") (pinfunction "B_1") (pintype "passive"))
      (node (ref "R24") (pin "2") (pinfunction "2_2") (pintype "passive"))
    )
    (net (code "92") (name "Net-(R27-Pad1)") (class "Default")
      (node (ref "R27") (pin "1") (pinfunction "1_1") (pintype "passive"))
      (node (ref "R28") (pin "1") (pinfunction "1_1") (pintype "passive"))
      (node (ref "RPI") (pin "1") (pinfunction "1_1") (pintype "passive"))
    )
    (net (code "93") (name "Net-(RELAIS1A-KL)") (class "Default")
      (node (ref "RELAIS1") (pin "1") (pinfunction "KL_1") (pintype "passive"))
      (node (ref "U1") (pin "1") (pinfunction "IP+_1") (pintype "bidirectional"))
      (node (ref "U1") (pin "2") (pinfunction "IP+_2") (pintype "bidirectional"))
    )
    (net (code "94") (name "Net-(RELAIS2A-KL)") (class "Default")
      (node (ref "RELAIS2") (pin "1") (pinfunction "KL_1") (pintype "passive"))
      (node (ref "U2") (pin "1") (pinfunction "IP+_1") (pintype "bidirectional"))
      (node (ref "U2") (pin "2") (pinfunction "IP+_2") (pintype "bidirectional"))
    )
    (net (code "95") (name "Net-(TELEINFOA-KL)") (class "Default")
      (node (ref "R4") (pin "1") (pinfunction "1_1") (pintype "passive"))
      (node (ref "TELEINFO") (pin "1") (pinfunction "KL_1") (pintype "passive"))
    )
    (net (code "96") (name "Net-(U1-FILT)") (class "Default")
      (node (ref "C8") (pin "1") (pinfunction "1_1") (pintype "passive"))
      (node (ref "U1") (pin "6") (pinfunction "FILT_6") (pintype "bidirectional"))
    )
    (net (code "97") (name "Net-(U2-FILT)") (class "Default")
      (node (ref "C11") (pin "1") (pinfunction "1_1") (pintype "passive"))
      (node (ref "U2") (pin "6") (pinfunction "FILT_6") (pintype "bidirectional"))
    )
    (net (code "98") (name "unconnected-(IC4-RA3{slash}AN3{slash}C1INB{slash}VREF+-Pad22)") (class "Default")
      (node (ref "IC4") (pin "22") (pinfunction "RA3/AN3/C1INB/VREF+_22") (pintype "bidirectional"))
    )
    (net (code "99") (name "unconnected-(U$1-PadDC_IN+)") (class "Default")
      (node (ref "U$1") (pin "DC_IN+") (pinfunction "DC_IN+_DC_IN+") (pintype "bidirectional"))
    )
    (net (code "100") (name "unconnected-(U$1-PadDC_IN-)") (class "Default")
      (node (ref "U$1") (pin "DC_IN-") (pinfunction "DC_IN-_DC_IN-") (pintype "bidirectional"))
    )
    (net (code "101") (name "unconnected-(USB-Pad1)") (class "Default")
      (node (ref "USB") (pin "1") (pinfunction "1_1") (pintype "passive"))
    )
    (net (code "102") (name "unconnected-(USB-Pad4)") (class "Default")
      (node (ref "USB") (pin "4") (pinfunction "4_4") (pintype "passive"))
    )
  )
)
